# MCU_USB.net
KiCad netlist of a schematic drawn in Altium Designer
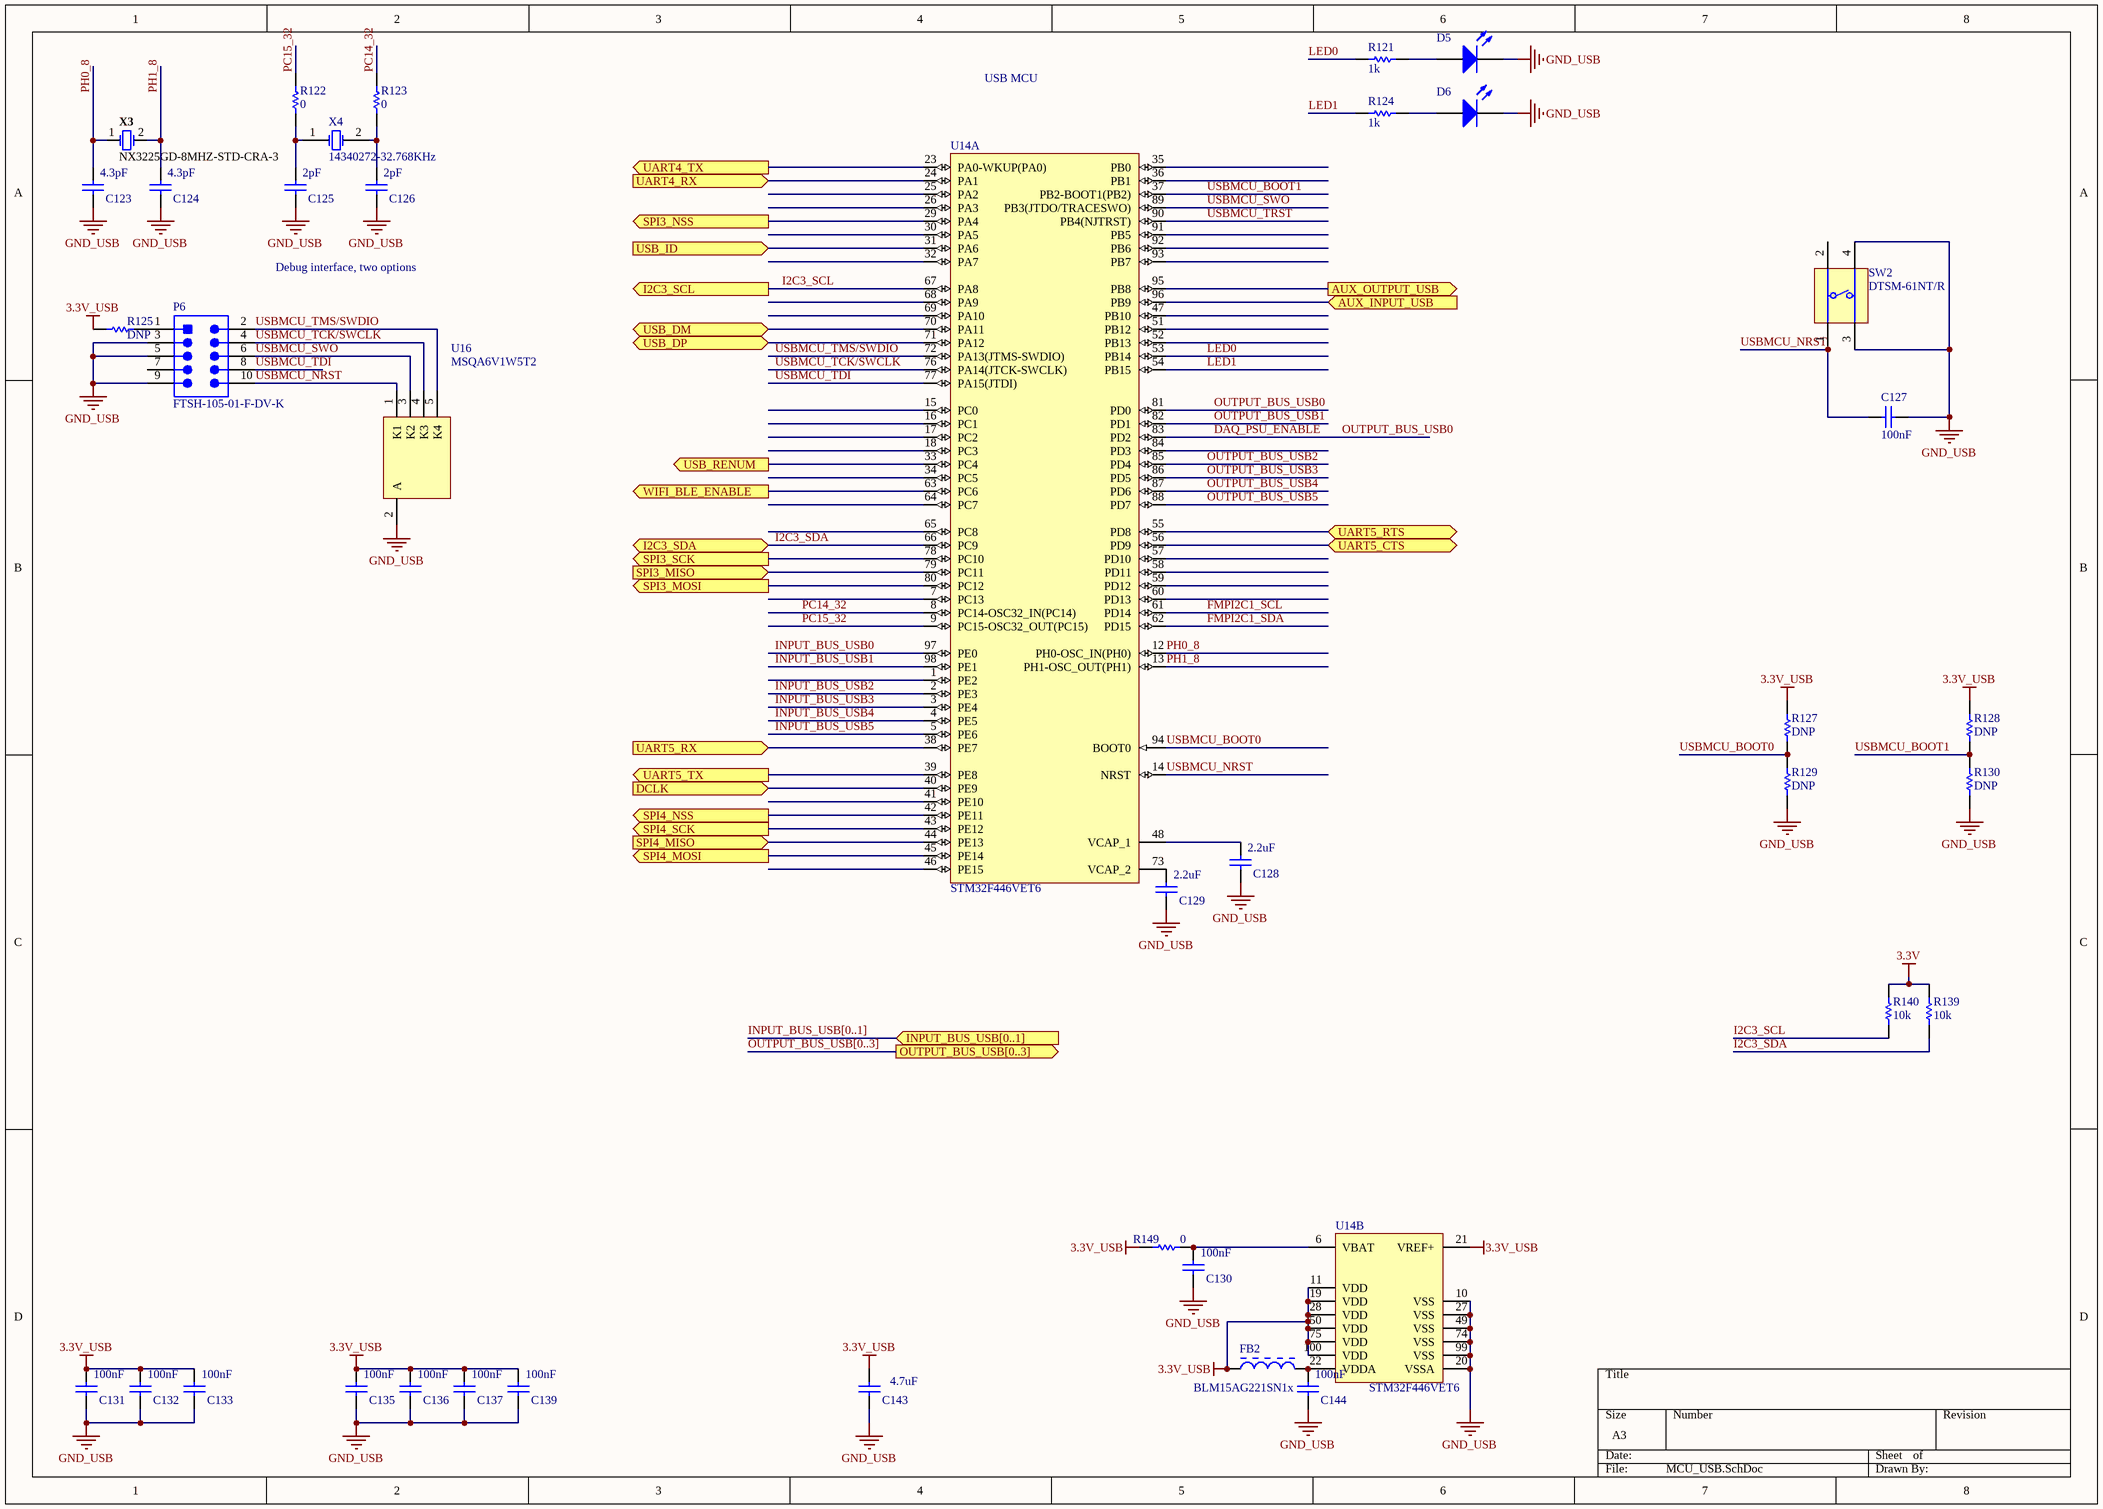
[diagram p0: MCU_USB.SchDoc]

(export (version "E")
  (design (tool "Eeschema 10.0.6"))
  (components
    (comp (ref "C123")
      (value "4.3pF")
      (footprint "CAPC0402(1005)60_L")
      (description "0402 (1005 Metric) Chip Capacitor")
      (fields (field (name "Comment") "CAP0402"))
      (libsource (lib "Altium Content Vault") (part "CMP-1590-00004-1"))
    )
    (comp (ref "C124")
      (value "4.3pF")
      (footprint "CAPC0402(1005)60_L")
      (description "0402 (1005 Metric) Chip Capacitor")
      (fields (field (name "Comment") "CAP0402"))
      (libsource (lib "Altium Content Vault") (part "CMP-1590-00004-1"))
    )
    (comp (ref "C125")
      (value "2pF")
      (footprint "CAPC0402(1005)60_L")
      (description "0402 (1005 Metric) Chip Capacitor")
      (fields (field (name "Comment") "CAP0402"))
      (libsource (lib "Altium Content Vault") (part "CMP-1590-00004-1"))
    )
    (comp (ref "C126")
      (value "2pF")
      (footprint "CAPC0402(1005)60_L")
      (description "0402 (1005 Metric) Chip Capacitor")
      (fields (field (name "Comment") "CAP0402"))
      (libsource (lib "Altium Content Vault") (part "CMP-1590-00004-1"))
    )
    (comp (ref "C127")
      (value "100nF")
      (footprint "CAPC0402(1005)60_L")
      (description "0402 (1005 Metric) Chip Capacitor")
      (fields (field (name "Comment") "CAP0402"))
      (libsource (lib "Altium Content Vault") (part "CMP-1590-00004-1"))
    )
    (comp (ref "C128")
      (value "2.2uF")
      (footprint "CAPC0402(1005)60_L")
      (description "0402 (1005 Metric) Chip Capacitor")
      (fields (field (name "Comment") "CAP0402"))
      (libsource (lib "Altium Content Vault") (part "CMP-1590-00004-1"))
    )
    (comp (ref "C129")
      (value "2.2uF")
      (footprint "CAPC0402(1005)60_L")
      (description "0402 (1005 Metric) Chip Capacitor")
      (fields (field (name "Comment") "CAP0402"))
      (libsource (lib "Altium Content Vault") (part "CMP-1590-00004-1"))
    )
    (comp (ref "C130")
      (value "100nF")
      (footprint "CAPC0402(1005)60_L")
      (description "0402 (1005 Metric) Chip Capacitor")
      (fields (field (name "Comment") "CAP0402"))
      (libsource (lib "Altium Content Vault") (part "CMP-1590-00004-1"))
    )
    (comp (ref "C131")
      (value "100nF")
      (footprint "CAPC0402(1005)60_L")
      (description "0402 (1005 Metric) Chip Capacitor")
      (fields (field (name "Comment") "CAP0402"))
      (libsource (lib "Altium Content Vault") (part "CMP-1590-00004-1"))
    )
    (comp (ref "C132")
      (value "100nF")
      (footprint "CAPC0402(1005)60_L")
      (description "0402 (1005 Metric) Chip Capacitor")
      (fields (field (name "Comment") "CAP0402"))
      (libsource (lib "Altium Content Vault") (part "CMP-1590-00004-1"))
    )
    (comp (ref "C133")
      (value "100nF")
      (footprint "CAPC0402(1005)60_L")
      (description "0402 (1005 Metric) Chip Capacitor")
      (fields (field (name "Comment") "CAP0402"))
      (libsource (lib "Altium Content Vault") (part "CMP-1590-00004-1"))
    )
    (comp (ref "C135")
      (value "100nF")
      (footprint "CAPC0402(1005)60_L")
      (description "0402 (1005 Metric) Chip Capacitor")
      (fields (field (name "Comment") "CAP0402"))
      (libsource (lib "Altium Content Vault") (part "CMP-1590-00004-1"))
    )
    (comp (ref "C136")
      (value "100nF")
      (footprint "CAPC0402(1005)60_L")
      (description "0402 (1005 Metric) Chip Capacitor")
      (fields (field (name "Comment") "CAP0402"))
      (libsource (lib "Altium Content Vault") (part "CMP-1590-00004-1"))
    )
    (comp (ref "C137")
      (value "100nF")
      (footprint "CAPC0402(1005)60_L")
      (description "0402 (1005 Metric) Chip Capacitor")
      (fields (field (name "Comment") "CAP0402"))
      (libsource (lib "Altium Content Vault") (part "CMP-1590-00004-1"))
    )
    (comp (ref "C139")
      (value "100nF")
      (footprint "CAPC0402(1005)60_L")
      (description "0402 (1005 Metric) Chip Capacitor")
      (fields (field (name "Comment") "CAP0402"))
      (libsource (lib "Altium Content Vault") (part "CMP-1590-00004-1"))
    )
    (comp (ref "C143")
      (value "4.7uF")
      (footprint "CAPC0805(2012)145_L")
      (description "0805 (2012 Metric) Chip Capacitor")
      (fields (field (name "Comment") "CAP0805"))
      (libsource (lib "Altium Content Vault") (part "CMP-1590-00003-1"))
    )
    (comp (ref "C144")
      (value "100nF")
      (footprint "CAPC0402(1005)60_L")
      (description "0402 (1005 Metric) Chip Capacitor")
      (fields (field (name "Comment") "CAP0402"))
      (libsource (lib "Altium Content Vault") (part "CMP-1590-00004-1"))
    )
    (comp (ref "D5")
      (value "Green_LED_150060GS75000")
      (footprint "Green_LED_150060GS75000")
      (description "WURTH ELEKTRONIK  150060GS75000  LED, Green, SMD, 30 mA, 3.2 V, 520 nm")
      (fields
        (field (name "MANUFACTURER PART NUMBER") "150060GS75000")
        (field (name "MANUFACTURER") "WURTH ELEKTRONIK")
      )
      (libsource (lib "Kilian_UCC_Library") (part "Green_LED_150060GS75000"))
    )
    (comp (ref "D6")
      (value "Green_LED_150060GS75000")
      (footprint "Green_LED_150060GS75000")
      (description "WURTH ELEKTRONIK  150060GS75000  LED, Green, SMD, 30 mA, 3.2 V, 520 nm")
      (fields
        (field (name "MANUFACTURER PART NUMBER") "150060GS75000")
        (field (name "MANUFACTURER") "WURTH ELEKTRONIK")
      )
      (libsource (lib "Kilian_UCC_Library") (part "Green_LED_150060GS75000"))
    )
    (comp (ref "FB2")
      (value "BLM15AG221SN1x")
      (footprint "MURA-BLM15AG221SN1x_V")
      (description "Chip Bead, 220 Ohm, +/- 25 %, 100 MHz, 300 mA, -55 to 125 degC, 0402 (1005 Metric), RoHS")
      (fields (field (name "TOLERANCE") "25%"))
      (libsource (lib "Altium Content Vault") (part "BEAD-2"))
    )
    (comp (ref "P6")
      (value "FTSH-105-01-F-DV-K")
      (footprint "SMTC-FTSH-105-01-L-DV-K_V")
      (description "Male Header, Pitch 1.27 mm, 2 x 5 Position, Height 6.12 mm, RoHS, Tube")
      (fields (field (name "MANUFACTURER") "Samtec"))
      (libsource (lib "Altium Content Vault") (part "CN-2P-M-R10"))
    )
    (comp (ref "R121")
      (value "1k")
      (footprint "RESC0402(1005)_L")
      (description "0402 (1005 Metric) Chip Resistor")
      (fields (field (name "Comment") "RES0402"))
      (libsource (lib "Altium Content Vault") (part "CMP-1591-00004-1"))
    )
    (comp (ref "R122")
      (value "0")
      (footprint "RESC0402(1005)_L")
      (description "0402 (1005 Metric) Chip Resistor")
      (fields (field (name "Comment") "RES0402"))
      (libsource (lib "Altium Content Vault") (part "CMP-1591-00004-1"))
    )
    (comp (ref "R123")
      (value "0")
      (footprint "RESC0402(1005)_L")
      (description "0402 (1005 Metric) Chip Resistor")
      (fields (field (name "Comment") "RES0402"))
      (libsource (lib "Altium Content Vault") (part "CMP-1591-00004-1"))
    )
    (comp (ref "R124")
      (value "1k")
      (footprint "RESC0402(1005)_L")
      (description "0402 (1005 Metric) Chip Resistor")
      (fields (field (name "Comment") "RES0402"))
      (libsource (lib "Altium Content Vault") (part "CMP-1591-00004-1"))
    )
    (comp (ref "R125")
      (value "DNP")
      (footprint "RESC0402(1005)_L")
      (description "0402 (1005 Metric) Chip Resistor")
      (fields (field (name "Comment") "RES0402"))
      (libsource (lib "Altium Content Vault") (part "CMP-1591-00004-1"))
    )
    (comp (ref "R127")
      (value "DNP")
      (footprint "RESC0402(1005)_L")
      (description "0402 (1005 Metric) Chip Resistor")
      (fields (field (name "Comment") "RES0402"))
      (libsource (lib "Altium Content Vault") (part "CMP-1591-00004-1"))
    )
    (comp (ref "R128")
      (value "DNP")
      (footprint "RESC0402(1005)_L")
      (description "0402 (1005 Metric) Chip Resistor")
      (fields (field (name "Comment") "RES0402"))
      (libsource (lib "Altium Content Vault") (part "CMP-1591-00004-1"))
    )
    (comp (ref "R129")
      (value "DNP")
      (footprint "RESC0402(1005)_L")
      (description "0402 (1005 Metric) Chip Resistor")
      (fields (field (name "Comment") "RES0402"))
      (libsource (lib "Altium Content Vault") (part "CMP-1591-00004-1"))
    )
    (comp (ref "R130")
      (value "DNP")
      (footprint "RESC0402(1005)_L")
      (description "0402 (1005 Metric) Chip Resistor")
      (fields (field (name "Comment") "RES0402"))
      (libsource (lib "Altium Content Vault") (part "CMP-1591-00004-1"))
    )
    (comp (ref "R139")
      (value "10k")
      (footprint "RESC0402(1005)_L")
      (description "0402 (1005 Metric) Chip Resistor")
      (fields (field (name "Comment") "RES0402"))
      (libsource (lib "Altium Content Vault") (part "CMP-1591-00004-1"))
    )
    (comp (ref "R140")
      (value "10k")
      (footprint "RESC0402(1005)_L")
      (description "0402 (1005 Metric) Chip Resistor")
      (fields (field (name "Comment") "RES0402"))
      (libsource (lib "Altium Content Vault") (part "CMP-1591-00004-1"))
    )
    (comp (ref "R149")
      (value "0")
      (footprint "RESC0402(1005)_L")
      (description "0402 (1005 Metric) Chip Resistor")
      (fields (field (name "Comment") "RES0402"))
      (libsource (lib "Altium Content Vault") (part "CMP-1591-00004-1"))
    )
    (comp (ref "SW2")
      (value "DTSM-61NT/R")
      (footprint "DIPT-DTSM-6_V")
      (description "Switch, SPNO Push Button SMD")
      (fields (field (name "MANUFACTURER") "Diptronics"))
      (libsource (lib "Altium Content Vault") (part "DIPT-DTSM-6"))
    )
    (comp (ref "U14")
      (value "STM32F446VET6")
      (footprint "STM-LQFP100_M")
      (libsource (lib "Altium Content Vault") (part "MC-ARM-STM32F446-LQFP100"))
    )
    (comp (ref "U16")
      (value "MSQA6V1W5T2")
      (footprint "ONSC-SC70-5-419A-02_V")
      (description "Quad Array ESD Protection Diodes with Low Clamping Voltage, 5-Pin SC70, Tape and Reel")
      (fields (field (name "MANUFACTURER") "On Semiconductor"))
      (libsource (lib "Altium Content Vault") (part "ONSC-MSQA6V1W5-SC70-5-419A-02"))
    )
    (comp (ref "X3")
      (value "NX3225GD-8MHZ-STD-CRA-3")
      (footprint "NDK-NX3225GD-8MHZ-STD-CRA-3_V")
      (description "Crystal Unit, 8 MHz, 8 pF, -40 to 150 degC, 2-Pin SMD, RoHS, Tape and Reel")
      (fields (field (name "MANUFACTURER") "NDK"))
      (libsource (lib "Altium Content Vault") (part "CMP-2000-07595-1"))
    )
    (comp (ref "X4")
      (value "14340272-32.768KHz")
      (footprint "ITTI-14340272-32.768KHz-2_V")
      (description "Crystal, 32.768 KHz, -40 to 85 degC, 3.2 x 1.5 x 0.9 mm SMD")
      (fields (field (name "MANUFACTURER") "ITTI"))
      (libsource (lib "Altium Content Vault") (part "ITTI-14340272-2"))
    )
  )
  (nets
    (net (code "1") (name "/AUX_INPUT_USB") (class "Default")
      (node (ref "U14") (pin "96") (pinfunction "PB9_96") (pintype "bidirectional"))
    )
    (net (code "2") (name "/AUX_OUTPUT_USB") (class "Default")
      (node (ref "U14") (pin "95") (pinfunction "PB8_95") (pintype "bidirectional"))
    )
    (net (code "3") (name "/DCLK") (class "Default")
      (node (ref "U14") (pin "40") (pinfunction "PE9_40") (pintype "bidirectional"))
    )
    (net (code "4") (name "/FMPI2C1_SCL") (class "Default")
      (node (ref "U14") (pin "61") (pinfunction "PD14_61") (pintype "bidirectional"))
    )
    (net (code "5") (name "/FMPI2C1_SDA") (class "Default")
      (node (ref "U14") (pin "62") (pinfunction "PD15_62") (pintype "bidirectional"))
    )
    (net (code "6") (name "/I2C3_SCL") (class "Default")
      (node (ref "R140") (pin "1") (pinfunction "1_1") (pintype "passive"))
      (node (ref "U14") (pin "67") (pinfunction "PA8_67") (pintype "bidirectional"))
    )
    (net (code "7") (name "/I2C3_SDA") (class "Default")
      (node (ref "R139") (pin "1") (pinfunction "1_1") (pintype "passive"))
      (node (ref "U14") (pin "66") (pinfunction "PC9_66") (pintype "bidirectional"))
    )
    (net (code "8") (name "/INPUT_BUS_USB0") (class "Default")
      (node (ref "U14") (pin "97") (pinfunction "PE0_97") (pintype "bidirectional"))
    )
    (net (code "9") (name "/INPUT_BUS_USB1") (class "Default")
      (node (ref "U14") (pin "98") (pinfunction "PE1_98") (pintype "bidirectional"))
    )
    (net (code "10") (name "/INPUT_BUS_USB2") (class "Default")
      (node (ref "U14") (pin "2") (pinfunction "PE3_2") (pintype "bidirectional"))
    )
    (net (code "11") (name "/INPUT_BUS_USB3") (class "Default")
      (node (ref "U14") (pin "3") (pinfunction "PE4_3") (pintype "bidirectional"))
    )
    (net (code "12") (name "/INPUT_BUS_USB4") (class "Default")
      (node (ref "U14") (pin "4") (pinfunction "PE5_4") (pintype "bidirectional"))
    )
    (net (code "13") (name "/INPUT_BUS_USB5") (class "Default")
      (node (ref "U14") (pin "5") (pinfunction "PE6_5") (pintype "bidirectional"))
    )
    (net (code "15") (name "/LED0") (class "Default")
      (node (ref "R121") (pin "1") (pinfunction "1_1") (pintype "passive"))
      (node (ref "U14") (pin "53") (pinfunction "PB14_53") (pintype "bidirectional"))
    )
    (net (code "16") (name "/LED1") (class "Default")
      (node (ref "R124") (pin "1") (pinfunction "1_1") (pintype "passive"))
      (node (ref "U14") (pin "54") (pinfunction "PB15_54") (pintype "bidirectional"))
    )
    (net (code "17") (name "/OUTPUT_BUS_USB0") (class "Default")
      (node (ref "U14") (pin "81") (pinfunction "PD0_81") (pintype "bidirectional"))
      (node (ref "U14") (pin "83") (pinfunction "PD2_83") (pintype "bidirectional"))
    )
    (net (code "18") (name "/OUTPUT_BUS_USB1") (class "Default")
      (node (ref "U14") (pin "82") (pinfunction "PD1_82") (pintype "bidirectional"))
    )
    (net (code "19") (name "/OUTPUT_BUS_USB2") (class "Default")
      (node (ref "U14") (pin "85") (pinfunction "PD4_85") (pintype "bidirectional"))
    )
    (net (code "20") (name "/OUTPUT_BUS_USB3") (class "Default")
      (node (ref "U14") (pin "86") (pinfunction "PD5_86") (pintype "bidirectional"))
    )
    (net (code "21") (name "/OUTPUT_BUS_USB4") (class "Default")
      (node (ref "U14") (pin "87") (pinfunction "PD6_87") (pintype "bidirectional"))
    )
    (net (code "22") (name "/OUTPUT_BUS_USB5") (class "Default")
      (node (ref "U14") (pin "88") (pinfunction "PD7_88") (pintype "bidirectional"))
    )
    (net (code "24") (name "/PC14_32") (class "Default")
      (node (ref "R123") (pin "1") (pinfunction "1_1") (pintype "passive"))
      (node (ref "U14") (pin "8") (pinfunction "PC14-OSC32_IN(PC14)_8") (pintype "bidirectional"))
    )
    (net (code "25") (name "/PC15_32") (class "Default")
      (node (ref "R122") (pin "1") (pinfunction "1_1") (pintype "passive"))
      (node (ref "U14") (pin "9") (pinfunction "PC15-OSC32_OUT(PC15)_9") (pintype "bidirectional"))
    )
    (net (code "26") (name "/PH0_8") (class "Default")
      (node (ref "C123") (pin "1") (pinfunction "1_1") (pintype "passive"))
      (node (ref "U14") (pin "12") (pinfunction "PH0-OSC_IN(PH0)_12") (pintype "bidirectional"))
      (node (ref "X3") (pin "1") (pinfunction "1_1") (pintype "passive"))
    )
    (net (code "27") (name "/PH1_8") (class "Default")
      (node (ref "C124") (pin "1") (pinfunction "1_1") (pintype "passive"))
      (node (ref "U14") (pin "13") (pinfunction "PH1-OSC_OUT(PH1)_13") (pintype "bidirectional"))
      (node (ref "X3") (pin "2") (pinfunction "2_2") (pintype "passive"))
    )
    (net (code "28") (name "/SPI3_MISO") (class "Default")
      (node (ref "U14") (pin "79") (pinfunction "PC11_79") (pintype "bidirectional"))
    )
    (net (code "29") (name "/SPI3_MOSI") (class "Default")
      (node (ref "U14") (pin "80") (pinfunction "PC12_80") (pintype "bidirectional"))
    )
    (net (code "30") (name "/SPI3_NSS") (class "Default")
      (node (ref "U14") (pin "29") (pinfunction "PA4_29") (pintype "bidirectional"))
    )
    (net (code "31") (name "/SPI3_SCK") (class "Default")
      (node (ref "U14") (pin "78") (pinfunction "PC10_78") (pintype "bidirectional"))
    )
    (net (code "32") (name "/SPI4_MISO") (class "Default")
      (node (ref "U14") (pin "44") (pinfunction "PE13_44") (pintype "bidirectional"))
    )
    (net (code "33") (name "/SPI4_MOSI") (class "Default")
      (node (ref "U14") (pin "45") (pinfunction "PE14_45") (pintype "bidirectional"))
    )
    (net (code "34") (name "/SPI4_NSS") (class "Default")
      (node (ref "U14") (pin "42") (pinfunction "PE11_42") (pintype "bidirectional"))
    )
    (net (code "35") (name "/SPI4_SCK") (class "Default")
      (node (ref "U14") (pin "43") (pinfunction "PE12_43") (pintype "bidirectional"))
    )
    (net (code "36") (name "/UART4_RX") (class "Default")
      (node (ref "U14") (pin "24") (pinfunction "PA1_24") (pintype "bidirectional"))
    )
    (net (code "37") (name "/UART4_TX") (class "Default")
      (node (ref "U14") (pin "23") (pinfunction "PA0-WKUP(PA0)_23") (pintype "bidirectional"))
    )
    (net (code "38") (name "/UART5_CTS") (class "Default")
      (node (ref "U14") (pin "56") (pinfunction "PD9_56") (pintype "bidirectional"))
    )
    (net (code "39") (name "/UART5_RTS") (class "Default")
      (node (ref "U14") (pin "55") (pinfunction "PD8_55") (pintype "bidirectional"))
    )
    (net (code "40") (name "/UART5_RX") (class "Default")
      (node (ref "U14") (pin "38") (pinfunction "PE7_38") (pintype "bidirectional"))
    )
    (net (code "41") (name "/UART5_TX") (class "Default")
      (node (ref "U14") (pin "39") (pinfunction "PE8_39") (pintype "bidirectional"))
    )
    (net (code "42") (name "/USBMCU_BOOT0") (class "Default")
      (node (ref "R127") (pin "1") (pinfunction "1_1") (pintype "passive"))
      (node (ref "R129") (pin "2") (pinfunction "2_2") (pintype "passive"))
      (node (ref "U14") (pin "94") (pinfunction "BOOT0_94") (pintype "input"))
    )
    (net (code "43") (name "/USBMCU_BOOT1") (class "Default")
      (node (ref "R128") (pin "1") (pinfunction "1_1") (pintype "passive"))
      (node (ref "R130") (pin "2") (pinfunction "2_2") (pintype "passive"))
      (node (ref "U14") (pin "37") (pinfunction "PB2-BOOT1(PB2)_37") (pintype "bidirectional"))
    )
    (net (code "44") (name "/USBMCU_NRST") (class "Default")
      (node (ref "C127") (pin "1") (pinfunction "1_1") (pintype "passive"))
      (node (ref "P6") (pin "10") (pinfunction "10_10") (pintype "passive"))
      (node (ref "SW2") (pin "1") (pinfunction "T1_1") (pintype "passive"))
      (node (ref "U14") (pin "14") (pinfunction "NRST_14") (pintype "bidirectional"))
      (node (ref "U16") (pin "1") (pinfunction "K1_1") (pintype "passive"))
    )
    (net (code "45") (name "/USBMCU_SWO") (class "Default")
      (node (ref "P6") (pin "6") (pinfunction "6_6") (pintype "passive"))
      (node (ref "U14") (pin "89") (pinfunction "PB3(JTDO/TRACESWO)_89") (pintype "bidirectional"))
      (node (ref "U16") (pin "3") (pinfunction "K2_3") (pintype "passive"))
    )
    (net (code "46") (name "/USBMCU_TCK{slash}SWCLK") (class "Default")
      (node (ref "P6") (pin "4") (pinfunction "4_4") (pintype "passive"))
      (node (ref "U14") (pin "76") (pinfunction "PA14(JTCK-SWCLK)_76") (pintype "bidirectional"))
      (node (ref "U16") (pin "4") (pinfunction "K3_4") (pintype "passive"))
    )
    (net (code "47") (name "/USBMCU_TDI") (class "Default")
      (node (ref "P6") (pin "8") (pinfunction "8_8") (pintype "passive"))
      (node (ref "U14") (pin "77") (pinfunction "PA15(JTDI)_77") (pintype "bidirectional"))
    )
    (net (code "48") (name "/USBMCU_TMS{slash}SWDIO") (class "Default")
      (node (ref "P6") (pin "2") (pinfunction "2_2") (pintype "passive"))
      (node (ref "U14") (pin "72") (pinfunction "PA13(JTMS-SWDIO)_72") (pintype "bidirectional"))
      (node (ref "U16") (pin "5") (pinfunction "K4_5") (pintype "passive"))
    )
    (net (code "49") (name "/USBMCU_TRST") (class "Default")
      (node (ref "U14") (pin "90") (pinfunction "PB4(NJTRST)_90") (pintype "bidirectional"))
    )
    (net (code "50") (name "/USB_DM") (class "Default")
      (node (ref "U14") (pin "70") (pinfunction "PA11_70") (pintype "bidirectional"))
    )
    (net (code "51") (name "/USB_DP") (class "Default")
      (node (ref "U14") (pin "71") (pinfunction "PA12_71") (pintype "bidirectional"))
    )
    (net (code "52") (name "/USB_ID") (class "Default")
      (node (ref "U14") (pin "31") (pinfunction "PA6_31") (pintype "bidirectional"))
    )
    (net (code "53") (name "/USB_RENUM") (class "Default")
      (node (ref "U14") (pin "33") (pinfunction "PC4_33") (pintype "bidirectional"))
    )
    (net (code "54") (name "/WIFI_BLE_ENABLE") (class "Default")
      (node (ref "U14") (pin "63") (pinfunction "PC6_63") (pintype "bidirectional"))
    )
    (net (code "55") (name "3.3V") (class "Default")
      (node (ref "R139") (pin "2") (pinfunction "2_2") (pintype "passive"))
      (node (ref "R140") (pin "2") (pinfunction "2_2") (pintype "passive"))
    )
    (net (code "56") (name "3.3V_USB") (class "Default")
      (node (ref "C131") (pin "1") (pinfunction "1_1") (pintype "passive"))
      (node (ref "C132") (pin "1") (pinfunction "1_1") (pintype "passive"))
      (node (ref "C133") (pin "1") (pinfunction "1_1") (pintype "passive"))
      (node (ref "C135") (pin "1") (pinfunction "1_1") (pintype "passive"))
      (node (ref "C136") (pin "1") (pinfunction "1_1") (pintype "passive"))
      (node (ref "C137") (pin "1") (pinfunction "1_1") (pintype "passive"))
      (node (ref "C139") (pin "1") (pinfunction "1_1") (pintype "passive"))
      (node (ref "C143") (pin "2") (pinfunction "2_2") (pintype "passive"))
      (node (ref "FB2") (pin "1") (pinfunction "1_1") (pintype "passive"))
      (node (ref "R125") (pin "2") (pinfunction "2_2") (pintype "passive"))
      (node (ref "R127") (pin "2") (pinfunction "2_2") (pintype "passive"))
      (node (ref "R128") (pin "2") (pinfunction "2_2") (pintype "passive"))
      (node (ref "R149") (pin "2") (pinfunction "2_2") (pintype "passive"))
      (node (ref "U14") (pin "100") (pinfunction "VDD_100") (pintype "power_in"))
      (node (ref "U14") (pin "11") (pinfunction "VDD_11") (pintype "power_in"))
      (node (ref "U14") (pin "19") (pinfunction "VDD_19") (pintype "power_in"))
      (node (ref "U14") (pin "21") (pinfunction "VREF+_21") (pintype "power_in"))
      (node (ref "U14") (pin "28") (pinfunction "VDD_28") (pintype "power_in"))
      (node (ref "U14") (pin "50") (pinfunction "VDD_50") (pintype "power_in"))
      (node (ref "U14") (pin "75") (pinfunction "VDD_75") (pintype "power_in"))
    )
    (net (code "57") (name "GND_USB") (class "Default")
      (node (ref "C123") (pin "2") (pinfunction "2_2") (pintype "passive"))
      (node (ref "C124") (pin "2") (pinfunction "2_2") (pintype "passive"))
      (node (ref "C125") (pin "2") (pinfunction "2_2") (pintype "passive"))
      (node (ref "C126") (pin "2") (pinfunction "2_2") (pintype "passive"))
      (node (ref "C127") (pin "2") (pinfunction "2_2") (pintype "passive"))
      (node (ref "C128") (pin "2") (pinfunction "2_2") (pintype "passive"))
      (node (ref "C129") (pin "2") (pinfunction "2_2") (pintype "passive"))
      (node (ref "C130") (pin "2") (pinfunction "2_2") (pintype "passive"))
      (node (ref "C131") (pin "2") (pinfunction "2_2") (pintype "passive"))
      (node (ref "C132") (pin "2") (pinfunction "2_2") (pintype "passive"))
      (node (ref "C133") (pin "2") (pinfunction "2_2") (pintype "passive"))
      (node (ref "C135") (pin "2") (pinfunction "2_2") (pintype "passive"))
      (node (ref "C136") (pin "2") (pinfunction "2_2") (pintype "passive"))
      (node (ref "C137") (pin "2") (pinfunction "2_2") (pintype "passive"))
      (node (ref "C139") (pin "2") (pinfunction "2_2") (pintype "passive"))
      (node (ref "C143") (pin "1") (pinfunction "1_1") (pintype "passive"))
      (node (ref "C144") (pin "2") (pinfunction "2_2") (pintype "passive"))
      (node (ref "D5") (pin "1") (pinfunction "1_1") (pintype "passive"))
      (node (ref "D6") (pin "1") (pinfunction "1_1") (pintype "passive"))
      (node (ref "P6") (pin "3") (pinfunction "3_3") (pintype "passive"))
      (node (ref "P6") (pin "5") (pinfunction "5_5") (pintype "passive"))
      (node (ref "P6") (pin "9") (pinfunction "9_9") (pintype "passive"))
      (node (ref "R129") (pin "1") (pinfunction "1_1") (pintype "passive"))
      (node (ref "R130") (pin "1") (pinfunction "1_1") (pintype "passive"))
      (node (ref "SW2") (pin "3") (pinfunction "T3_3") (pintype "passive"))
      (node (ref "SW2") (pin "4") (pinfunction "T3_4") (pintype "passive"))
      (node (ref "U14") (pin "10") (pinfunction "VSS_10") (pintype "power_in"))
      (node (ref "U14") (pin "20") (pinfunction "VSSA_20") (pintype "power_in"))
      (node (ref "U14") (pin "27") (pinfunction "VSS_27") (pintype "power_in"))
      (node (ref "U14") (pin "49") (pinfunction "VSS_49") (pintype "power_in"))
      (node (ref "U14") (pin "74") (pinfunction "VSS_74") (pintype "power_in"))
      (node (ref "U14") (pin "99") (pinfunction "VSS_99") (pintype "power_in"))
      (node (ref "U16") (pin "2") (pinfunction "A_2") (pintype "passive"))
    )
    (net (code "58") (name "Net-(D5-Pad2)") (class "Default")
      (node (ref "D5") (pin "2") (pinfunction "2_2") (pintype "passive"))
      (node (ref "R121") (pin "2") (pinfunction "2_2") (pintype "passive"))
    )
    (net (code "59") (name "Net-(D6-Pad2)") (class "Default")
      (node (ref "D6") (pin "2") (pinfunction "2_2") (pintype "passive"))
      (node (ref "R124") (pin "2") (pinfunction "2_2") (pintype "passive"))
    )
    (net (code "60") (name "Net-(P6-Pad1)") (class "Default")
      (node (ref "P6") (pin "1") (pinfunction "1_1") (pintype "passive"))
      (node (ref "R125") (pin "1") (pinfunction "1_1") (pintype "passive"))
    )
    (net (code "61") (name "Net-(U14A-VCAP_1)") (class "Default")
      (node (ref "C128") (pin "1") (pinfunction "1_1") (pintype "passive"))
      (node (ref "U14") (pin "48") (pinfunction "VCAP_1_48") (pintype "passive"))
    )
    (net (code "62") (name "Net-(U14A-VCAP_2)") (class "Default")
      (node (ref "C129") (pin "1") (pinfunction "1_1") (pintype "passive"))
      (node (ref "U14") (pin "73") (pinfunction "VCAP_2_73") (pintype "passive"))
    )
    (net (code "63") (name "Net-(U14B-VBAT)") (class "Default")
      (node (ref "C130") (pin "1") (pinfunction "1_1") (pintype "passive"))
      (node (ref "R149") (pin "1") (pinfunction "1_1") (pintype "passive"))
      (node (ref "U14") (pin "6") (pinfunction "VBAT_6") (pintype "power_in"))
    )
    (net (code "64") (name "Net-(U14B-VDDA)") (class "Default")
      (node (ref "C144") (pin "1") (pinfunction "1_1") (pintype "passive"))
      (node (ref "FB2") (pin "2") (pinfunction "2_2") (pintype "passive"))
      (node (ref "U14") (pin "22") (pinfunction "VDDA_22") (pintype "power_in"))
    )
    (net (code "65") (name "Net-(X4-X1)") (class "Default")
      (node (ref "C125") (pin "1") (pinfunction "1_1") (pintype "passive"))
      (node (ref "R122") (pin "2") (pinfunction "2_2") (pintype "passive"))
      (node (ref "X4") (pin "1") (pinfunction "X1_1") (pintype "passive"))
    )
    (net (code "66") (name "Net-(X4-X2)") (class "Default")
      (node (ref "C126") (pin "1") (pinfunction "1_1") (pintype "passive"))
      (node (ref "R123") (pin "2") (pinfunction "2_2") (pintype "passive"))
      (node (ref "X4") (pin "2") (pinfunction "X2_2") (pintype "passive"))
    )
    (net (code "67") (name "unconnected-(P6-Pad7)") (class "Default")
      (node (ref "P6") (pin "7") (pinfunction "7_7") (pintype "passive"))
    )
    (net (code "68") (name "unconnected-(SW2-T2-Pad2)") (class "Default")
      (node (ref "SW2") (pin "2") (pinfunction "T2_2") (pintype "passive"))
    )
    (net (code "69") (name "unconnected-(U14A-PA2-Pad25)") (class "Default")
      (node (ref "U14") (pin "25") (pinfunction "PA2_25") (pintype "bidirectional"))
    )
    (net (code "70") (name "unconnected-(U14A-PA3-Pad26)") (class "Default")
      (node (ref "U14") (pin "26") (pinfunction "PA3_26") (pintype "bidirectional"))
    )
    (net (code "71") (name "unconnected-(U14A-PA5-Pad30)") (class "Default")
      (node (ref "U14") (pin "30") (pinfunction "PA5_30") (pintype "bidirectional"))
    )
    (net (code "72") (name "unconnected-(U14A-PA7-Pad32)") (class "Default")
      (node (ref "U14") (pin "32") (pinfunction "PA7_32") (pintype "bidirectional"))
    )
    (net (code "73") (name "unconnected-(U14A-PA9-Pad68)") (class "Default")
      (node (ref "U14") (pin "68") (pinfunction "PA9_68") (pintype "bidirectional"))
    )
    (net (code "74") (name "unconnected-(U14A-PA10-Pad69)") (class "Default")
      (node (ref "U14") (pin "69") (pinfunction "PA10_69") (pintype "bidirectional"))
    )
    (net (code "75") (name "unconnected-(U14A-PB0-Pad35)") (class "Default")
      (node (ref "U14") (pin "35") (pinfunction "PB0_35") (pintype "bidirectional"))
    )
    (net (code "76") (name "unconnected-(U14A-PB1-Pad36)") (class "Default")
      (node (ref "U14") (pin "36") (pinfunction "PB1_36") (pintype "bidirectional"))
    )
    (net (code "77") (name "unconnected-(U14A-PB5-Pad91)") (class "Default")
      (node (ref "U14") (pin "91") (pinfunction "PB5_91") (pintype "bidirectional"))
    )
    (net (code "78") (name "unconnected-(U14A-PB6-Pad92)") (class "Default")
      (node (ref "U14") (pin "92") (pinfunction "PB6_92") (pintype "bidirectional"))
    )
    (net (code "79") (name "unconnected-(U14A-PB7-Pad93)") (class "Default")
      (node (ref "U14") (pin "93") (pinfunction "PB7_93") (pintype "bidirectional"))
    )
    (net (code "80") (name "unconnected-(U14A-PB10-Pad47)") (class "Default")
      (node (ref "U14") (pin "47") (pinfunction "PB10_47") (pintype "bidirectional"))
    )
    (net (code "81") (name "unconnected-(U14A-PB12-Pad51)") (class "Default")
      (node (ref "U14") (pin "51") (pinfunction "PB12_51") (pintype "bidirectional"))
    )
    (net (code "82") (name "unconnected-(U14A-PB13-Pad52)") (class "Default")
      (node (ref "U14") (pin "52") (pinfunction "PB13_52") (pintype "bidirectional"))
    )
    (net (code "83") (name "unconnected-(U14A-PC0-Pad15)") (class "Default")
      (node (ref "U14") (pin "15") (pinfunction "PC0_15") (pintype "bidirectional"))
    )
    (net (code "84") (name "unconnected-(U14A-PC1-Pad16)") (class "Default")
      (node (ref "U14") (pin "16") (pinfunction "PC1_16") (pintype "bidirectional"))
    )
    (net (code "85") (name "unconnected-(U14A-PC2-Pad17)") (class "Default")
      (node (ref "U14") (pin "17") (pinfunction "PC2_17") (pintype "bidirectional"))
    )
    (net (code "86") (name "unconnected-(U14A-PC3-Pad18)") (class "Default")
      (node (ref "U14") (pin "18") (pinfunction "PC3_18") (pintype "bidirectional"))
    )
    (net (code "87") (name "unconnected-(U14A-PC5-Pad34)") (class "Default")
      (node (ref "U14") (pin "34") (pinfunction "PC5_34") (pintype "bidirectional"))
    )
    (net (code "88") (name "unconnected-(U14A-PC7-Pad64)") (class "Default")
      (node (ref "U14") (pin "64") (pinfunction "PC7_64") (pintype "bidirectional"))
    )
    (net (code "89") (name "unconnected-(U14A-PC8-Pad65)") (class "Default")
      (node (ref "U14") (pin "65") (pinfunction "PC8_65") (pintype "bidirectional"))
    )
    (net (code "90") (name "unconnected-(U14A-PC13-Pad7)") (class "Default")
      (node (ref "U14") (pin "7") (pinfunction "PC13_7") (pintype "bidirectional"))
    )
    (net (code "91") (name "unconnected-(U14A-PD3-Pad84)") (class "Default")
      (node (ref "U14") (pin "84") (pinfunction "PD3_84") (pintype "bidirectional"))
    )
    (net (code "92") (name "unconnected-(U14A-PD10-Pad57)") (class "Default")
      (node (ref "U14") (pin "57") (pinfunction "PD10_57") (pintype "bidirectional"))
    )
    (net (code "93") (name "unconnected-(U14A-PD11-Pad58)") (class "Default")
      (node (ref "U14") (pin "58") (pinfunction "PD11_58") (pintype "bidirectional"))
    )
    (net (code "94") (name "unconnected-(U14A-PD12-Pad59)") (class "Default")
      (node (ref "U14") (pin "59") (pinfunction "PD12_59") (pintype "bidirectional"))
    )
    (net (code "95") (name "unconnected-(U14A-PD13-Pad60)") (class "Default")
      (node (ref "U14") (pin "60") (pinfunction "PD13_60") (pintype "bidirectional"))
    )
    (net (code "96") (name "unconnected-(U14A-PE2-Pad1)") (class "Default")
      (node (ref "U14") (pin "1") (pinfunction "PE2_1") (pintype "bidirectional"))
    )
    (net (code "97") (name "unconnected-(U14A-PE10-Pad41)") (class "Default")
      (node (ref "U14") (pin "41") (pinfunction "PE10_41") (pintype "bidirectional"))
    )
    (net (code "98") (name "unconnected-(U14A-PE15-Pad46)") (class "Default")
      (node (ref "U14") (pin "46") (pinfunction "PE15_46") (pintype "bidirectional"))
    )
  )
)
